# LedStrip_Example.net
KiCad netlist of a schematic drawn in EasyEDA Pro
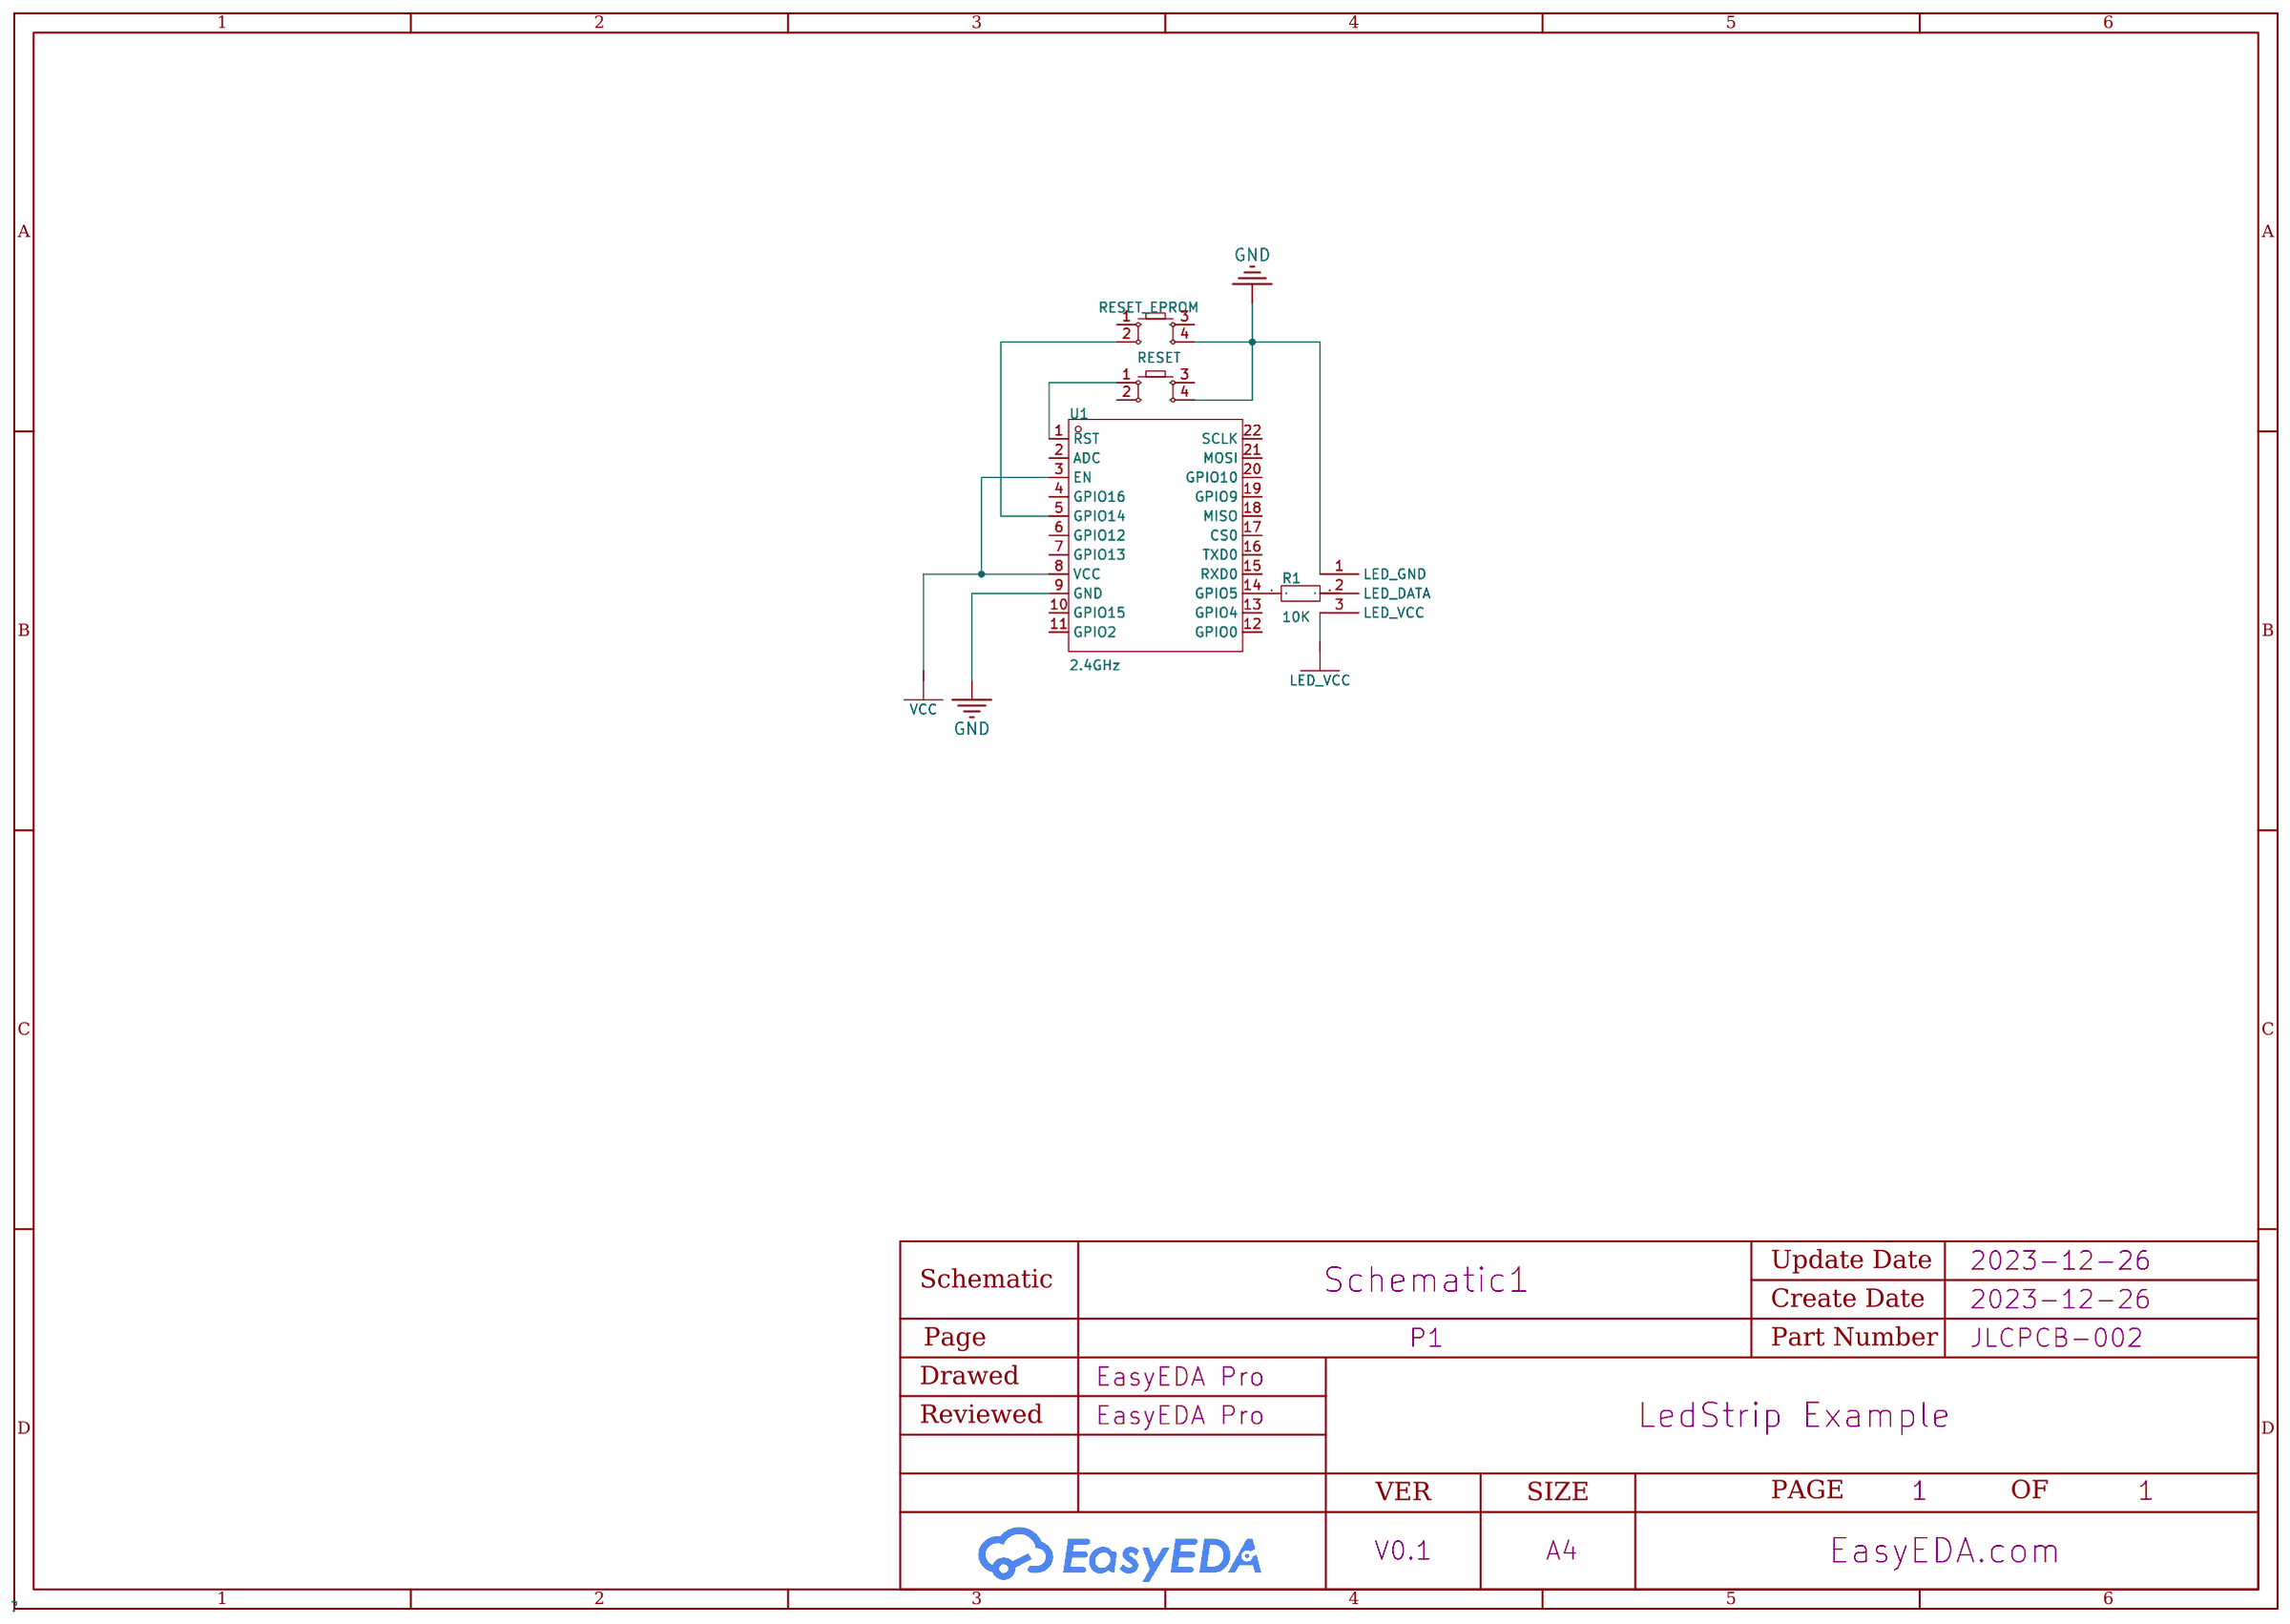
[diagram p0: schematic sheet]

(export (version "E")
  (design (tool "Eeschema 10.0.6"))
  (components
    (comp (ref "R1") (value "10K") (footprint "easyedapro:R0603") (libsource (lib "easyedapro") (part "Res")))
    (comp (ref "RESET")
      (value "~")
      (footprint "easyedapro:KEY-TH_4P-L6.0-W6.0-P3.90-LS6.5")
      (libsource (lib "easyedapro") (part "轻触按键"))
    )
    (comp (ref "RESET_EPROM")
      (value "~")
      (footprint "easyedapro:KEY-TH_4P-L6.0-W6.0-P3.90-LS6.5")
      (libsource (lib "easyedapro") (part "轻触按键"))
    )
    (comp (ref "U1")
      (value "2.4GHz")
      (footprint "easyedapro:WIFIM-SMD_ESP-12F-ESP8266MOD")
      (fields
        (field (name "Manufacturer Part") "ESP-12F(ESP8266MOD)")
        (field (name "Manufacturer") "Ai-Thinker(安信可)")
      )
      (libsource (lib "easyedapro") (part "ESP-12F(ESP8266MOD)"))
    )
    (comp (ref "U2") (value "~") (libsource (lib "easyedapro") (part "3 pins for led")))
  )
  (nets
    (net (code "1") (name "GND") (class "Default")
      (node (ref "RESET") (pin "4") (pinfunction "4_4") (pintype "input"))
      (node (ref "RESET_EPROM") (pin "4") (pinfunction "4_4") (pintype "input"))
      (node (ref "U1") (pin "9") (pinfunction "GND_9") (pintype "input"))
      (node (ref "U2") (pin "1") (pinfunction "LED_GND_1") (pintype "input"))
    )
    (net (code "2") (name "LED_VCC") (class "Default")
      (node (ref "U2") (pin "3") (pinfunction "LED_VCC_3") (pintype "input"))
    )
    (net (code "3") (name "Net-(U1-GPIO5)") (class "Default")
      (node (ref "R1") (pin "1") (pinfunction "1_1") (pintype "input"))
      (node (ref "U1") (pin "14") (pinfunction "GPIO5_14") (pintype "input"))
    )
    (net (code "4") (name "Net-(U1-GPIO14)") (class "Default")
      (node (ref "RESET_EPROM") (pin "2") (pinfunction "2_2") (pintype "input"))
      (node (ref "U1") (pin "5") (pinfunction "GPIO14_5") (pintype "input"))
    )
    (net (code "5") (name "Net-(U1-RST)") (class "Default")
      (node (ref "RESET") (pin "1") (pinfunction "1_1") (pintype "input"))
      (node (ref "U1") (pin "1") (pinfunction "RST_1") (pintype "input"))
    )
    (net (code "6") (name "Net-(U2-LED_DATA)") (class "Default")
      (node (ref "R1") (pin "2") (pinfunction "2_2") (pintype "input"))
      (node (ref "U2") (pin "2") (pinfunction "LED_DATA_2") (pintype "input"))
    )
    (net (code "7") (name "VCC") (class "Default")
      (node (ref "U1") (pin "3") (pinfunction "EN_3") (pintype "input"))
      (node (ref "U1") (pin "8") (pinfunction "VCC_8") (pintype "input"))
    )
    (net (code "8") (name "unconnected-(RESET-Pad2)") (class "Default")
      (node (ref "RESET") (pin "2") (pinfunction "2_2") (pintype "input"))
    )
    (net (code "9") (name "unconnected-(RESET-Pad3)") (class "Default")
      (node (ref "RESET") (pin "3") (pinfunction "3_3") (pintype "input"))
    )
    (net (code "10") (name "unconnected-(RESET_EPROM-Pad1)") (class "Default")
      (node (ref "RESET_EPROM") (pin "1") (pinfunction "1_1") (pintype "input"))
    )
    (net (code "11") (name "unconnected-(RESET_EPROM-Pad3)") (class "Default")
      (node (ref "RESET_EPROM") (pin "3") (pinfunction "3_3") (pintype "input"))
    )
    (net (code "12") (name "unconnected-(U1-ADC-Pad2)") (class "Default")
      (node (ref "U1") (pin "2") (pinfunction "ADC_2") (pintype "input"))
    )
    (net (code "13") (name "unconnected-(U1-CS0-Pad17)") (class "Default")
      (node (ref "U1") (pin "17") (pinfunction "CS0_17") (pintype "input"))
    )
    (net (code "14") (name "unconnected-(U1-GPIO0-Pad12)") (class "Default")
      (node (ref "U1") (pin "12") (pinfunction "GPIO0_12") (pintype "input"))
    )
    (net (code "15") (name "unconnected-(U1-GPIO2-Pad11)") (class "Default")
      (node (ref "U1") (pin "11") (pinfunction "GPIO2_11") (pintype "input"))
    )
    (net (code "16") (name "unconnected-(U1-GPIO4-Pad13)") (class "Default")
      (node (ref "U1") (pin "13") (pinfunction "GPIO4_13") (pintype "input"))
    )
    (net (code "17") (name "unconnected-(U1-GPIO9-Pad19)") (class "Default")
      (node (ref "U1") (pin "19") (pinfunction "GPIO9_19") (pintype "input"))
    )
    (net (code "18") (name "unconnected-(U1-GPIO10-Pad20)") (class "Default")
      (node (ref "U1") (pin "20") (pinfunction "GPIO10_20") (pintype "input"))
    )
    (net (code "19") (name "unconnected-(U1-GPIO12-Pad6)") (class "Default")
      (node (ref "U1") (pin "6") (pinfunction "GPIO12_6") (pintype "input"))
    )
    (net (code "20") (name "unconnected-(U1-GPIO13-Pad7)") (class "Default")
      (node (ref "U1") (pin "7") (pinfunction "GPIO13_7") (pintype "input"))
    )
    (net (code "21") (name "unconnected-(U1-GPIO15-Pad10)") (class "Default")
      (node (ref "U1") (pin "10") (pinfunction "GPIO15_10") (pintype "input"))
    )
    (net (code "22") (name "unconnected-(U1-GPIO16-Pad4)") (class "Default")
      (node (ref "U1") (pin "4") (pinfunction "GPIO16_4") (pintype "input"))
    )
    (net (code "23") (name "unconnected-(U1-MISO-Pad18)") (class "Default")
      (node (ref "U1") (pin "18") (pinfunction "MISO_18") (pintype "input"))
    )
    (net (code "24") (name "unconnected-(U1-MOSI-Pad21)") (class "Default")
      (node (ref "U1") (pin "21") (pinfunction "MOSI_21") (pintype "input"))
    )
    (net (code "25") (name "unconnected-(U1-RXD0-Pad15)") (class "Default")
      (node (ref "U1") (pin "15") (pinfunction "RXD0_15") (pintype "input"))
    )
    (net (code "26") (name "unconnected-(U1-SCLK-Pad22)") (class "Default")
      (node (ref "U1") (pin "22") (pinfunction "SCLK_22") (pintype "input"))
    )
    (net (code "27") (name "unconnected-(U1-TXD0-Pad16)") (class "Default")
      (node (ref "U1") (pin "16") (pinfunction "TXD0_16") (pintype "input"))
    )
  )
)
